# ETAG_v8_u2270b_AOS2017.net
KiCad netlist of a schematic drawn in EAGLE
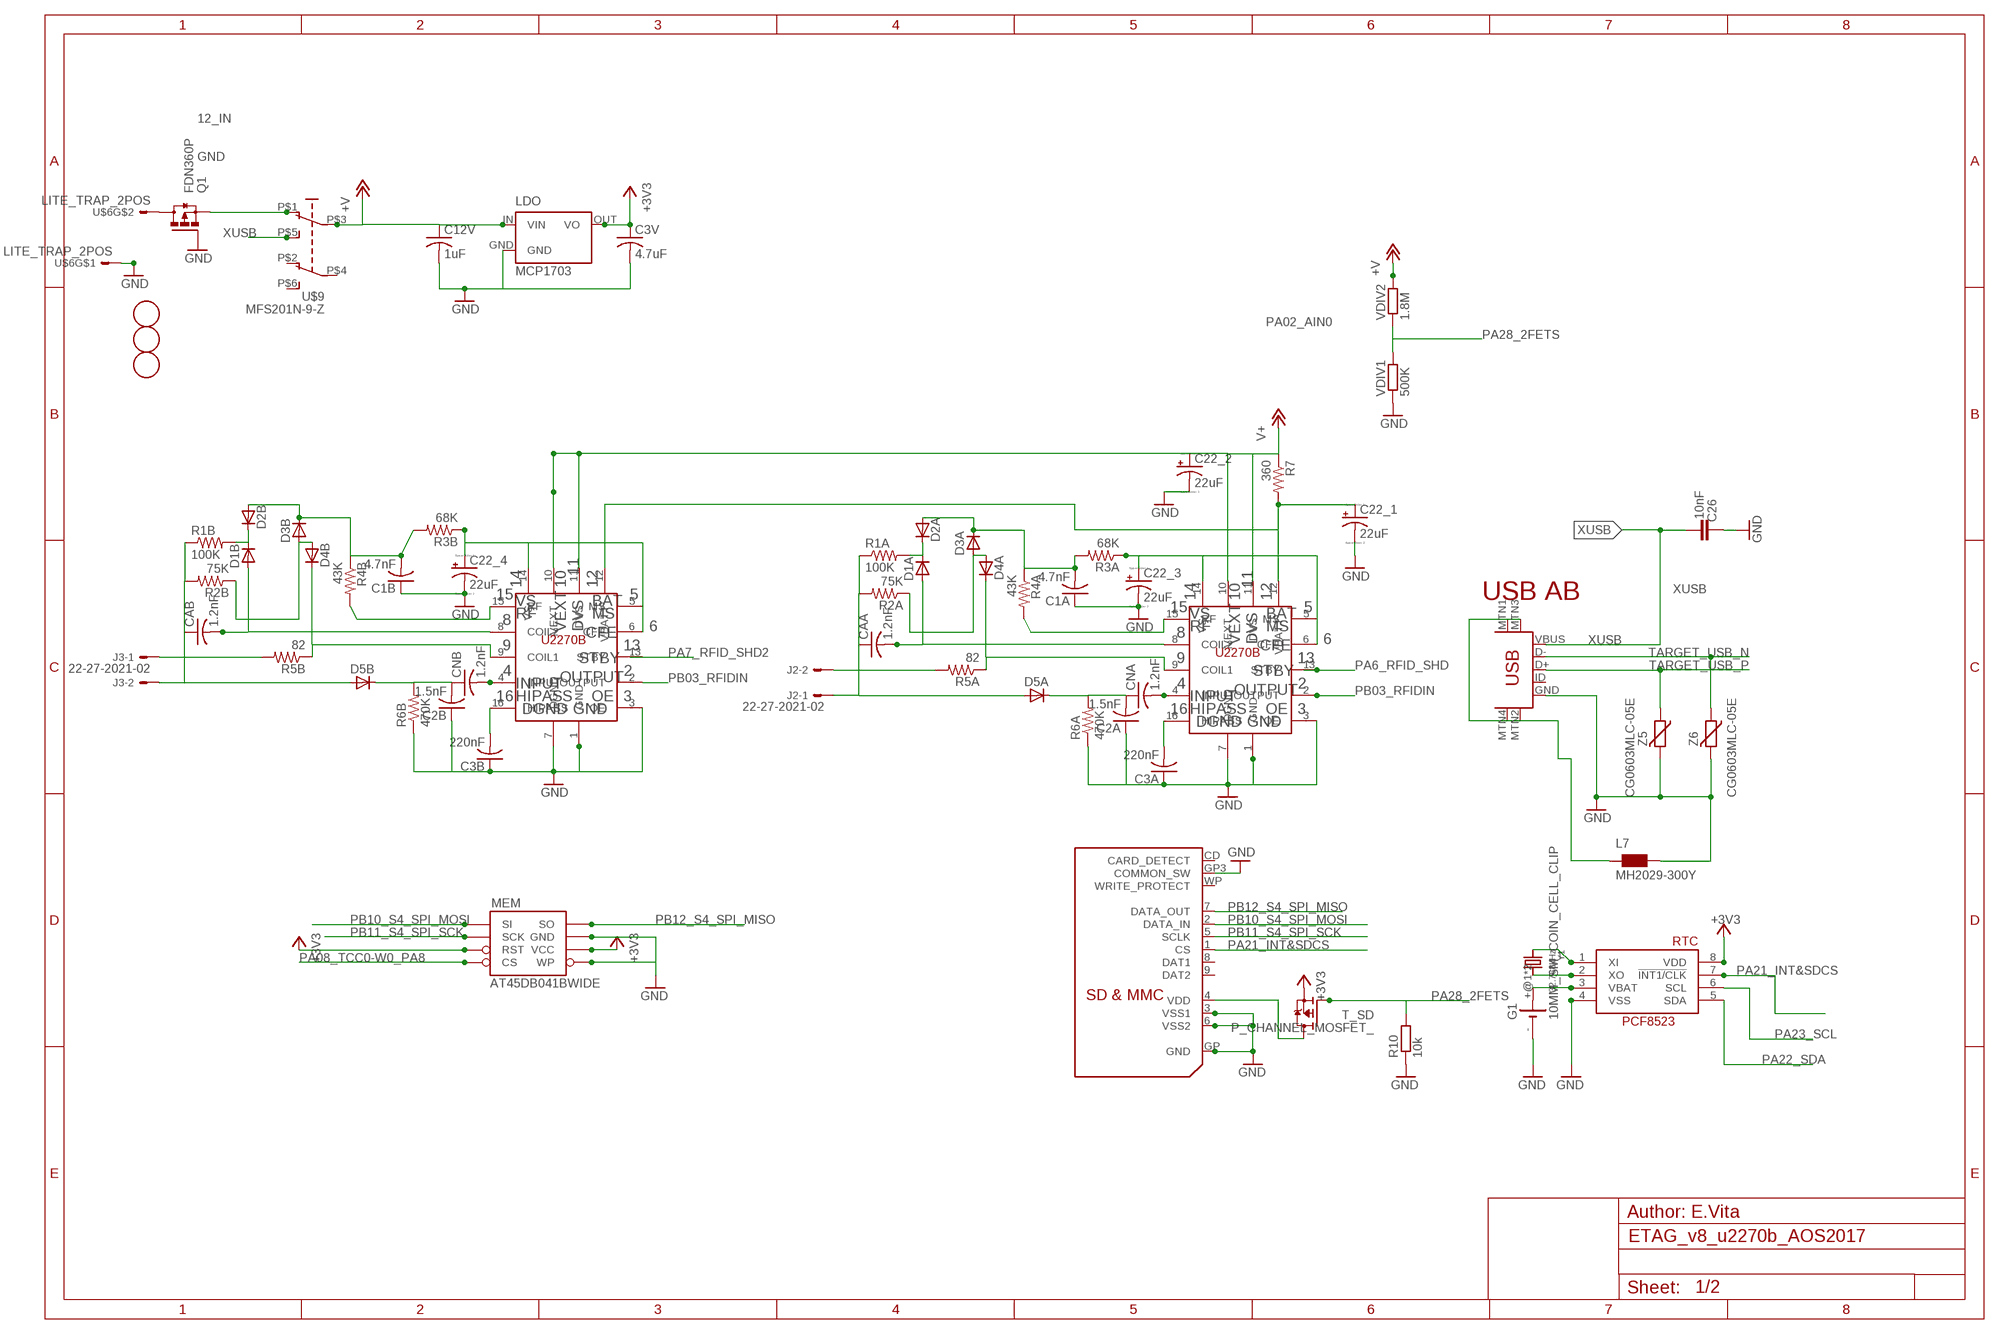
[diagram p0: schematic, sheet 1]
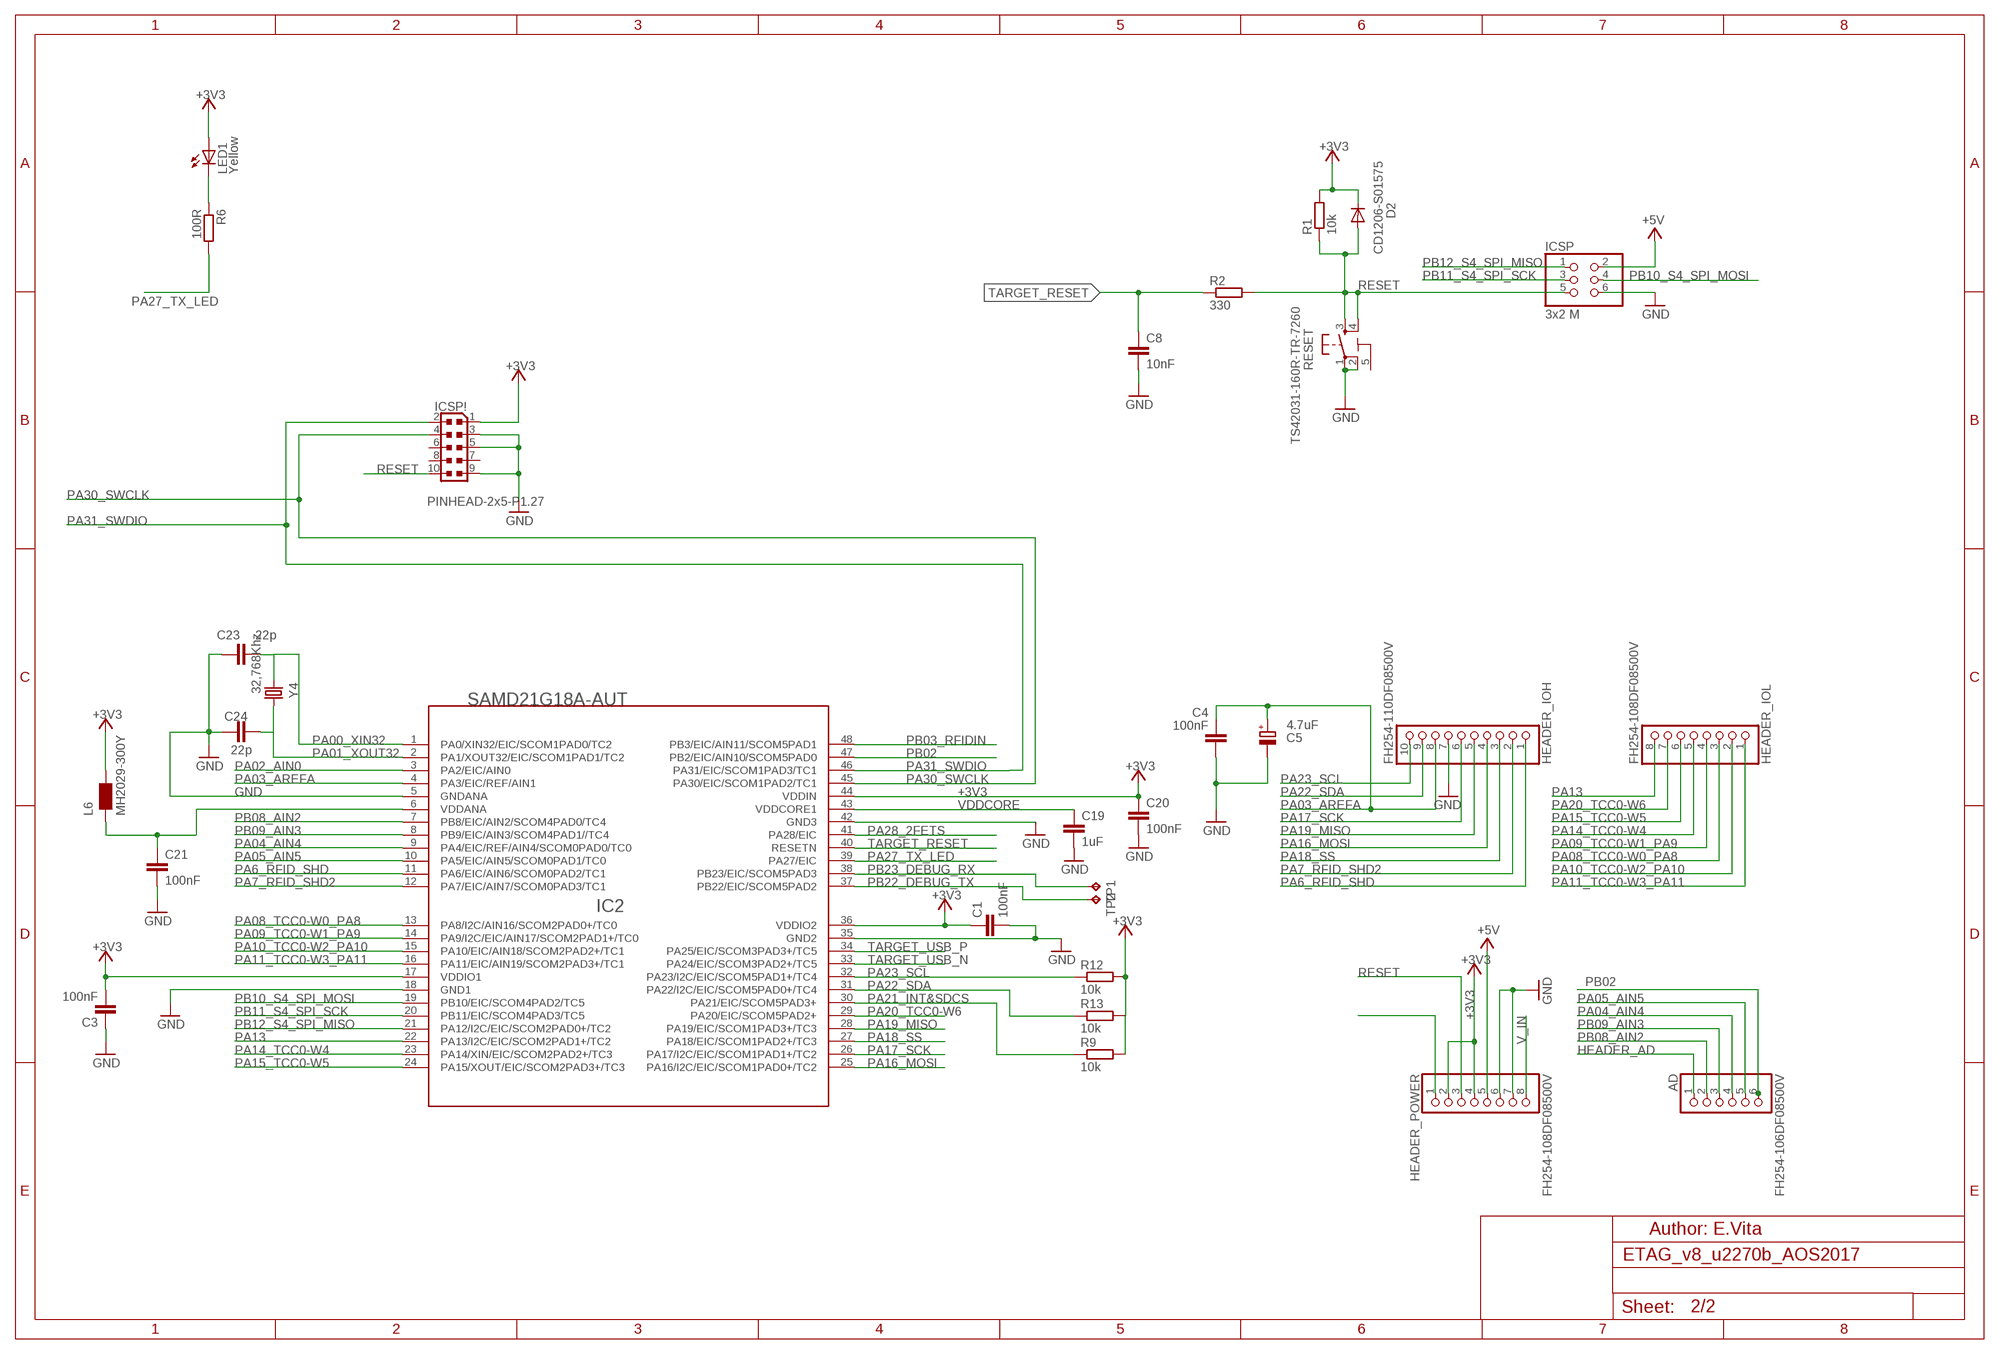
[diagram p1: schematic, sheet 2]

(export (version "E")
  (design (tool "Eeschema 10.0.6"))
  (components
    (comp (ref "AD")
      (value "FH254-106DF08500V")
      (footprint "eagle-import:1X06")
      (fields (field (name "PART_NUMBER") "20TW-535"))
      (libsource (lib "eagle-import") (part "1682_20TW-535_STD"))
    )
    (comp (ref "C1")
      (value "100nF")
      (footprint "eagle-import:C0603-ROUND")
      (fields (field (name "PART_NUMBER") "cl10b104kbnc"))
      (libsource (lib "eagle-import") (part "0015_100NF_0603"))
    )
    (comp (ref "C3")
      (value "100nF")
      (footprint "eagle-import:C0603-ROUND")
      (fields (field (name "PART_NUMBER") "cl10b104kbnc"))
      (libsource (lib "eagle-import") (part "0015_100NF_0603"))
    )
    (comp (ref "C4")
      (value "100nF")
      (footprint "eagle-import:C0603-ROUND")
      (fields (field (name "PART_NUMBER") "cl10b104kbnc"))
      (libsource (lib "eagle-import") (part "0015_100NF_0603"))
    )
    (comp (ref "C5")
      (value "4.7uF")
      (footprint "eagle-import:SMC_A")
      (fields (field (name "PART_NUMBER") "TAJA475M016RNJ"))
      (libsource (lib "eagle-import") (part "0474_TAJA475M016RNJ"))
    )
    (comp (ref "C8")
      (value "10nF")
      (footprint "eagle-import:C0603-ROUND")
      (fields (field (name "PART_NUMBER") "10nF_0603"))
      (libsource (lib "eagle-import") (part "0142_10NF_0603"))
    )
    (comp (ref "C19")
      (value "1uF")
      (footprint "eagle-import:C0603-ROUND")
      (fields (field (name "PART_NUMBER") "1uF_0603/GRM188R61E105KA12D"))
      (libsource (lib "eagle-import") (part "0006_1UF_0603/GRM188R61E105KA12D"))
    )
    (comp (ref "C20")
      (value "100nF")
      (footprint "eagle-import:C0603-ROUND")
      (fields (field (name "PART_NUMBER") "cl10b104kbnc"))
      (libsource (lib "eagle-import") (part "0015_100NF_0603"))
    )
    (comp (ref "C21")
      (value "100nF")
      (footprint "eagle-import:C0603-ROUND")
      (fields (field (name "PART_NUMBER") "cl10b104kbnc"))
      (libsource (lib "eagle-import") (part "0015_100NF_0603"))
    )
    (comp (ref "C23")
      (value "22p")
      (footprint "eagle-import:C0603-ROUND")
      (fields (field (name "PART_NUMBER") "22pF_0603"))
      (libsource (lib "eagle-import") (part "0014_22PF_0603"))
    )
    (comp (ref "C24")
      (value "22p")
      (footprint "eagle-import:C0603-ROUND")
      (fields (field (name "PART_NUMBER") "22pF_0603"))
      (libsource (lib "eagle-import") (part "0014_22PF_0603"))
    )
    (comp (ref "D2")
      (value "CD1206-S01575")
      (footprint "eagle-import:MINIMELF")
      (libsource (lib "eagle-import") (part "0012_CD1206-S01575"))
    )
    (comp (ref "HEADER_IOH")
      (value "FH254-110DF08500V")
      (footprint "eagle-import:1X10")
      (fields (field (name "PART_NUMBER") "20TW-537"))
      (libsource (lib "eagle-import") (part "1684_20TW-537"))
    )
    (comp (ref "HEADER_IOL")
      (value "FH254-108DF08500V")
      (footprint "eagle-import:1X08")
      (fields (field (name "PART_NUMBER") "20TW-536"))
      (libsource (lib "eagle-import") (part "1683_20TW-536"))
    )
    (comp (ref "HEADER_POWER")
      (value "FH254-108DF08500V")
      (footprint "eagle-import:1X08")
      (fields (field (name "PART_NUMBER") "20TW-536"))
      (libsource (lib "eagle-import") (part "1683_20TW-536"))
    )
    (comp (ref "IC2")
      (value "SAMD21G18A-AUT")
      (footprint "eagle-import:TQFP48-7X7")
      (libsource (lib "eagle-import") (part "1792_SAMD21G18A-AUT"))
    )
    (comp (ref "ICSP")
      (value "3x2 M")
      (footprint "eagle-import:2X03")
      (fields (field (name "PART_NUMBER") "PH254-203DF118A00V"))
      (libsource (lib "eagle-import") (part "0114_PH254-203DF118A00V"))
    )
    (comp (ref "ICSP!")
      (value "PINHEAD-2x5-P1.27")
      (footprint "eagle-import:PINHEAD_2X05_127")
      (libsource (lib "eagle-import") (part "0171_PH127-205DF055G00AROUND-PADS"))
    )
    (comp (ref "L6")
      (value "MH2029-300Y")
      (footprint "eagle-import:0805")
      (fields (field (name "PART_NUMBER") "BLM21PG300SN1D_/_MH2029-300Y"))
      (libsource (lib "eagle-import") (part "0001_BLM21PG300SN1D_/_MH2029-300Y"))
    )
    (comp (ref "LED1")
      (value "Yellow")
      (footprint "eagle-import:CHIPLED_0805")
      (fields (field (name "PART_NUMBER") "KPT-2012YC"))
      (libsource (lib "eagle-import") (part "0044_KPT-2012YC"))
    )
    (comp (ref "R1")
      (value "10k")
      (footprint "eagle-import:R0603-ROUND")
      (fields (field (name "PART_NUMBER") "CR0603JW103L"))
      (libsource (lib "eagle-import") (part "0028_CR0603JW103L"))
    )
    (comp (ref "R2")
      (value "330")
      (footprint "eagle-import:R0603-ROUND")
      (fields (field (name "PART_NUMBER") "330R_0603"))
      (libsource (lib "eagle-import") (part "0049_330R_0603"))
    )
    (comp (ref "R6")
      (value "100R")
      (footprint "eagle-import:R0603-ROUND")
      (fields (field (name "PART_NUMBER") "0R_0603"))
      (libsource (lib "eagle-import") (part "0233_0R_0603"))
    )
    (comp (ref "R9")
      (value "10k")
      (footprint "eagle-import:R0603-ROUND")
      (fields (field (name "PART_NUMBER") "CR0603JW103L"))
      (libsource (lib "eagle-import") (part "0028_CR0603JW103L"))
    )
    (comp (ref "R12")
      (value "10k")
      (footprint "eagle-import:R0603-ROUND")
      (fields (field (name "PART_NUMBER") "CR0603JW103L"))
      (libsource (lib "eagle-import") (part "0028_CR0603JW103L"))
    )
    (comp (ref "R13")
      (value "10k")
      (footprint "eagle-import:R0603-ROUND")
      (fields (field (name "PART_NUMBER") "CR0603JW103L"))
      (libsource (lib "eagle-import") (part "0028_CR0603JW103L"))
    )
    (comp (ref "RESET")
      (value "TS42031-160R-TR-7260")
      (footprint "eagle-import:TS42")
      (fields (field (name "PART_NUMBER") "IT-1157AHNP-160G-G_GTR"))
      (libsource (lib "eagle-import") (part "0946_TS42031-160W-TR-7260"))
    )
    (comp (ref "TP1")
      (value "TPTP15R")
      (footprint "eagle-import:TP15R")
      (libsource (lib "eagle-import") (part "TPTP15R"))
    )
    (comp (ref "TP2")
      (value "TPTP15R")
      (footprint "eagle-import:TP15R")
      (libsource (lib "eagle-import") (part "TPTP15R"))
    )
    (comp (ref "Y4")
      (value "32,768Khz")
      (footprint "eagle-import:RESONATOR_EPSON_FC_145")
      (fields (field (name "PART_NUMBER") "ABS07-32.768KHZ-T"))
      (libsource (lib "eagle-import") (part "0213_ABS07-32.768KHZ-T"))
    )
    (comp (ref "C1A")
      (value "4.7nF")
      (footprint "eagle-import:C0603-ROUND")
      (libsource (lib "eagle-import") (part "C-US"))
    )
    (comp (ref "C1B")
      (value "4.7nF")
      (footprint "eagle-import:C0603-ROUND")
      (libsource (lib "eagle-import") (part "C-US"))
    )
    (comp (ref "C2A")
      (value "1.5nF")
      (footprint "eagle-import:C0805")
      (libsource (lib "eagle-import") (part "C-USC0805"))
    )
    (comp (ref "C2B")
      (value "1.5nF")
      (footprint "eagle-import:C0805")
      (libsource (lib "eagle-import") (part "C-USC0805"))
    )
    (comp (ref "C3A")
      (value "220nF")
      (footprint "eagle-import:C0603-ROUND")
      (libsource (lib "eagle-import") (part "C-US"))
    )
    (comp (ref "C3B")
      (value "220nF")
      (footprint "eagle-import:C0603-ROUND")
      (libsource (lib "eagle-import") (part "C-US"))
    )
    (comp (ref "C3V")
      (value "4.7uF")
      (footprint "eagle-import:C0805")
      (libsource (lib "eagle-import") (part "C-USC0805"))
    )
    (comp (ref "C12V")
      (value "1uF")
      (footprint "eagle-import:C0805")
      (libsource (lib "eagle-import") (part "C-USC0805"))
    )
    (comp (ref "C22_1")
      (value "22uF")
      (footprint "eagle-import:153CLV-0505")
      (libsource (lib "eagle-import") (part "CPOL-US153CLV-0505"))
    )
    (comp (ref "C22_2")
      (value "22uF")
      (footprint "eagle-import:153CLV-0505")
      (libsource (lib "eagle-import") (part "CPOL-US153CLV-0505"))
    )
    (comp (ref "C22_3")
      (value "22uF")
      (footprint "eagle-import:153CLV-0505")
      (libsource (lib "eagle-import") (part "CPOL-US153CLV-0505"))
    )
    (comp (ref "C22_4")
      (value "22uF")
      (footprint "eagle-import:153CLV-0505")
      (libsource (lib "eagle-import") (part "CPOL-US153CLV-0505"))
    )
    (comp (ref "C26")
      (value "10nF")
      (footprint "eagle-import:C0603-ROUND")
      (fields (field (name "PART_NUMBER") "10nF_0603"))
      (libsource (lib "eagle-import") (part "0142_10NF_0603"))
    )
    (comp (ref "CAA")
      (value "1.2nF")
      (footprint "eagle-import:C0805")
      (libsource (lib "eagle-import") (part "C-USC0805"))
    )
    (comp (ref "CAB")
      (value "1.2nF")
      (footprint "eagle-import:C0805")
      (libsource (lib "eagle-import") (part "C-USC0805"))
    )
    (comp (ref "CNA")
      (value "1.2nF")
      (footprint "eagle-import:C0805")
      (libsource (lib "eagle-import") (part "C-USC0805"))
    )
    (comp (ref "CNB")
      (value "1.2nF")
      (footprint "eagle-import:C0805")
      (libsource (lib "eagle-import") (part "C-USC0805"))
    )
    (comp (ref "D1A")
      (value "D-GLASS_MELF")
      (footprint "eagle-import:SOT-23_2PAD")
      (libsource (lib "eagle-import") (part "D-GLASS_MELF"))
    )
    (comp (ref "D1B")
      (value "D-GLASS_MELF")
      (footprint "eagle-import:SOT-23_2PAD")
      (libsource (lib "eagle-import") (part "D-GLASS_MELF"))
    )
    (comp (ref "D2A")
      (value "D-GLASS_MELF")
      (footprint "eagle-import:SOT-23_2PAD")
      (libsource (lib "eagle-import") (part "D-GLASS_MELF"))
    )
    (comp (ref "D2B")
      (value "D-GLASS_MELF")
      (footprint "eagle-import:SOT-23_2PAD")
      (libsource (lib "eagle-import") (part "D-GLASS_MELF"))
    )
    (comp (ref "D3A")
      (value "D-GLASS_MELF")
      (footprint "eagle-import:SOT-23_2PAD")
      (libsource (lib "eagle-import") (part "D-GLASS_MELF"))
    )
    (comp (ref "D3B")
      (value "D-GLASS_MELF")
      (footprint "eagle-import:SOT-23_2PAD")
      (libsource (lib "eagle-import") (part "D-GLASS_MELF"))
    )
    (comp (ref "D4A")
      (value "D-GLASS_MELF")
      (footprint "eagle-import:SOT-23_2PAD")
      (libsource (lib "eagle-import") (part "D-GLASS_MELF"))
    )
    (comp (ref "D4B")
      (value "D-GLASS_MELF")
      (footprint "eagle-import:SOT-23_2PAD")
      (libsource (lib "eagle-import") (part "D-GLASS_MELF"))
    )
    (comp (ref "D5A")
      (value "D-GLASS_MELF")
      (footprint "eagle-import:SOT-23_2PAD")
      (libsource (lib "eagle-import") (part "D-GLASS_MELF"))
    )
    (comp (ref "D5B")
      (value "D-GLASS_MELF")
      (footprint "eagle-import:SOT-23_2PAD")
      (libsource (lib "eagle-import") (part "D-GLASS_MELF"))
    )
    (comp (ref "FD1")
      (value "FIDUCIALMOUNT")
      (footprint "eagle-import:FIDUCIA-MOUNT")
      (libsource (lib "eagle-import") (part "FIDUCIALMOUNT"))
    )
    (comp (ref "FD2")
      (value "FIDUCIALMOUNT")
      (footprint "eagle-import:FIDUCIA-MOUNT")
      (libsource (lib "eagle-import") (part "FIDUCIALMOUNT"))
    )
    (comp (ref "FD3")
      (value "FIDUCIALMOUNT")
      (footprint "eagle-import:FIDUCIA-MOUNT")
      (libsource (lib "eagle-import") (part "FIDUCIALMOUNT"))
    )
    (comp (ref "G1")
      (value "10MM_SM_COIN_CELL_CLIP")
      (footprint "eagle-import:10MM_SM_COIN_CELL_CLIP")
      (libsource (lib "eagle-import") (part "10MM_SM_COIN_CELL_CLIP"))
    )
    (comp (ref "J2")
      (value "22-27-2021-02")
      (footprint "eagle-import:6410-02")
      (libsource (lib "eagle-import") (part "22-?-0227-2021"))
    )
    (comp (ref "J3")
      (value "22-27-2021-02")
      (footprint "eagle-import:6410-02")
      (libsource (lib "eagle-import") (part "22-?-0227-2021"))
    )
    (comp (ref "L7")
      (value "MH2029-300Y")
      (footprint "eagle-import:0805")
      (fields (field (name "PART_NUMBER") "BLM21PG300SN1D_/_MH2029-300Y"))
      (libsource (lib "eagle-import") (part "0001_BLM21PG300SN1D_/_MH2029-300Y"))
    )
    (comp (ref "LDO")
      (value "MCP1703")
      (footprint "eagle-import:SOT89")
      (libsource (lib "eagle-import") (part "MCP1703"))
    )
    (comp (ref "MEM")
      (value "AT45DB041BWIDE")
      (footprint "eagle-import:SO08WIDE")
      (libsource (lib "eagle-import") (part "AT45DB041BWIDE"))
    )
    (comp (ref "Q1")
      (value "FDN360P")
      (footprint "eagle-import:SUPER-SOT3")
      (libsource (lib "eagle-import") (part "FDN360P"))
    )
    (comp (ref "R1A")
      (value "100K")
      (footprint "eagle-import:C0603-ROUND")
      (libsource (lib "eagle-import") (part "R-US_ROUND"))
    )
    (comp (ref "R1B")
      (value "100K")
      (footprint "eagle-import:C0603-ROUND")
      (libsource (lib "eagle-import") (part "R-US_ROUND"))
    )
    (comp (ref "R2A")
      (value "75K")
      (footprint "eagle-import:C0603-ROUND")
      (libsource (lib "eagle-import") (part "R-US_ROUND"))
    )
    (comp (ref "R2B")
      (value "75K")
      (footprint "eagle-import:C0603-ROUND")
      (libsource (lib "eagle-import") (part "R-US_ROUND"))
    )
    (comp (ref "R3A")
      (value "68K")
      (footprint "eagle-import:C0603-ROUND")
      (libsource (lib "eagle-import") (part "R-US_ROUND"))
    )
    (comp (ref "R3B")
      (value "68K")
      (footprint "eagle-import:C0603-ROUND")
      (libsource (lib "eagle-import") (part "R-US_ROUND"))
    )
    (comp (ref "R4A")
      (value "43K")
      (footprint "eagle-import:C0603-ROUND")
      (libsource (lib "eagle-import") (part "R-US_ROUND"))
    )
    (comp (ref "R4B")
      (value "43K")
      (footprint "eagle-import:C0603-ROUND")
      (libsource (lib "eagle-import") (part "R-US_ROUND"))
    )
    (comp (ref "R5A")
      (value "82")
      (footprint "eagle-import:C0603-ROUND")
      (libsource (lib "eagle-import") (part "R-US_ROUND"))
    )
    (comp (ref "R5B")
      (value "82")
      (footprint "eagle-import:C0603-ROUND")
      (libsource (lib "eagle-import") (part "R-US_ROUND"))
    )
    (comp (ref "R6A")
      (value "470K")
      (footprint "eagle-import:C0603-ROUND")
      (libsource (lib "eagle-import") (part "R-US_ROUND"))
    )
    (comp (ref "R6B")
      (value "470K")
      (footprint "eagle-import:C0603-ROUND")
      (libsource (lib "eagle-import") (part "R-US_ROUND"))
    )
    (comp (ref "R7")
      (value "360")
      (footprint "eagle-import:C0603-ROUND")
      (libsource (lib "eagle-import") (part "R-US_ROUND"))
    )
    (comp (ref "R10")
      (value "10k")
      (footprint "eagle-import:R0603-ROUND")
      (fields (field (name "PART_NUMBER") "CR0603JW103L"))
      (libsource (lib "eagle-import") (part "0028_CR0603JW103L"))
    )
    (comp (ref "RF_A")
      (value "U2270B")
      (footprint "eagle-import:SO16")
      (libsource (lib "eagle-import") (part "U2270B"))
    )
    (comp (ref "RF_B")
      (value "U2270B")
      (footprint "eagle-import:SO16")
      (libsource (lib "eagle-import") (part "U2270B"))
    )
    (comp (ref "RTC")
      (value "RTC_PCF8523T")
      (footprint "eagle-import:SOIC8_150MIL")
      (libsource (lib "eagle-import") (part "RTC_PCF8523T"))
    )
    (comp (ref "T_SD")
      (value "P_CHANNEL_MOSFET_")
      (footprint "eagle-import:SOT23")
      (libsource (lib "eagle-import") (part "P_CHANNEL_MOSFET_"))
    )
    (comp (ref "U$4")
      (value "SDMMC06132")
      (footprint "eagle-import:06132")
      (libsource (lib "eagle-import") (part "SDMMC06132"))
    )
    (comp (ref "U$6")
      (value "LITE_TRAP_2POS")
      (footprint "eagle-import:LITE_TRAP_MINI")
      (libsource (lib "eagle-import") (part "LITE_TRAP_2POS"))
    )
    (comp (ref "U$9")
      (value "MFS201N-9-Z")
      (footprint "eagle-import:MFS201N-9-Z")
      (libsource (lib "eagle-import") (part "MFS201N-9-Z"))
    )
    (comp (ref "USB")
      (value "USB-MINIB-5PIN")
      (footprint "eagle-import:USB-MINIB")
      (libsource (lib "eagle-import") (part "USB-MINIB-5PIN"))
    )
    (comp (ref "VDIV1")
      (value "500K")
      (footprint "eagle-import:R0603-ROUND")
      (libsource (lib "eagle-import") (part "2339_"))
    )
    (comp (ref "VDIV2")
      (value "1.8M")
      (footprint "eagle-import:R0603-ROUND")
      (fields (field (name "PART_NUMBER") "CR0603FW104L"))
      (libsource (lib "eagle-import") (part "2022_CR0603FW104L"))
    )
    (comp (ref "Y1")
      (value "32.768kHz")
      (footprint "eagle-import:CRYSTAL_8X3.8")
      (libsource (lib "eagle-import") (part "CRYSTAL8.0X3.8"))
    )
    (comp (ref "Z5")
      (value "CG0603MLC-05E")
      (footprint "eagle-import:CT_CN0603")
      (fields (field (name "PART_NUMBER") "BRNCG0603MLC-05E"))
      (libsource (lib "eagle-import") (part "0010_BRNCG0603MLC-05E"))
    )
    (comp (ref "Z6")
      (value "CG0603MLC-05E")
      (footprint "eagle-import:CT_CN0603")
      (fields (field (name "PART_NUMBER") "BRNCG0603MLC-05E"))
      (libsource (lib "eagle-import") (part "0010_BRNCG0603MLC-05E"))
    )
  )
  (nets
    (net (code "1") (name "+3V3") (class "Default")
      (node (ref "C1") (pin "1") (pinfunction "1_1") (pintype "passive"))
      (node (ref "C20") (pin "1") (pinfunction "1_1") (pintype "passive"))
      (node (ref "C3") (pin "2") (pinfunction "2_2") (pintype "passive"))
      (node (ref "C3V") (pin "1") (pinfunction "1_1") (pintype "passive"))
      (node (ref "D2") (pin "C") (pinfunction "C_C") (pintype "passive"))
      (node (ref "HEADER_POWER") (pin "2") (pinfunction "2_2") (pintype "passive"))
      (node (ref "HEADER_POWER") (pin "4") (pinfunction "4_4") (pintype "passive"))
      (node (ref "IC2") (pin "17") (pinfunction "VDDIO1_17") (pintype "power_in"))
      (node (ref "IC2") (pin "36") (pinfunction "VDDIO2_36") (pintype "power_in"))
      (node (ref "IC2") (pin "44") (pinfunction "VDDIN_44") (pintype "power_in"))
      (node (ref "ICSP!") (pin "1") (pinfunction "1_1") (pintype "passive"))
      (node (ref "L6") (pin "2") (pinfunction "2_2") (pintype "passive"))
      (node (ref "LDO") (pin "OUT") (pinfunction "VO_OUT") (pintype "output"))
      (node (ref "LED1") (pin "A") (pinfunction "A_A") (pintype "passive"))
      (node (ref "MEM") (pin "3") (pinfunction "RST_3") (pintype "bidirectional"))
      (node (ref "MEM") (pin "6") (pinfunction "VCC_6") (pintype "bidirectional"))
      (node (ref "R1") (pin "2") (pinfunction "2_2") (pintype "passive"))
      (node (ref "R12") (pin "2") (pinfunction "2_2") (pintype "passive"))
      (node (ref "R13") (pin "2") (pinfunction "2_2") (pintype "passive"))
      (node (ref "R9") (pin "2") (pinfunction "2_2") (pintype "passive"))
      (node (ref "RTC") (pin "8") (pinfunction "VDD_8") (pintype "power_in"))
      (node (ref "T_SD") (pin "2") (pinfunction "S_2") (pintype "passive"))
    )
    (net (code "2") (name "+5V") (class "Default")
      (node (ref "HEADER_POWER") (pin "5") (pinfunction "5_5") (pintype "passive"))
      (node (ref "ICSP") (pin "2") (pinfunction "2_2") (pintype "passive"))
    )
    (net (code "3") (name "5-GND") (class "Default")
      (node (ref "RESET") (pin "5") (pinfunction "5-GND_5") (pintype "power_in"))
    )
    (net (code "5") (name "12_IN") (class "Default")
      (node (ref "Q1") (pin "3") (pinfunction "D_3") (pintype "passive"))
      (node (ref "U$6") (pin "P$3") (pinfunction "S_P$3") (pintype "passive"))
      (node (ref "U$6") (pin "P$4") (pinfunction "S_P$4") (pintype "passive"))
    )
    (net (code "6") (name "GND") (class "Default")
      (node (ref "C1") (pin "2") (pinfunction "2_2") (pintype "passive"))
      (node (ref "C12V") (pin "2") (pinfunction "2_2") (pintype "passive"))
      (node (ref "C19") (pin "2") (pinfunction "2_2") (pintype "passive"))
      (node (ref "C1A") (pin "1") (pinfunction "1_1") (pintype "passive"))
      (node (ref "C1B") (pin "1") (pinfunction "1_1") (pintype "passive"))
      (node (ref "C20") (pin "2") (pinfunction "2_2") (pintype "passive"))
      (node (ref "C21") (pin "2") (pinfunction "2_2") (pintype "passive"))
      (node (ref "C22_1") (pin "-") (pinfunction "-_-") (pintype "passive"))
      (node (ref "C22_2") (pin "-") (pinfunction "-_-") (pintype "passive"))
      (node (ref "C22_3") (pin "-") (pinfunction "-_-") (pintype "passive"))
      (node (ref "C22_4") (pin "-") (pinfunction "-_-") (pintype "passive"))
      (node (ref "C23") (pin "1") (pinfunction "1_1") (pintype "passive"))
      (node (ref "C24") (pin "1") (pinfunction "1_1") (pintype "passive"))
      (node (ref "C26") (pin "2") (pinfunction "2_2") (pintype "passive"))
      (node (ref "C2A") (pin "1") (pinfunction "1_1") (pintype "passive"))
      (node (ref "C2B") (pin "1") (pinfunction "1_1") (pintype "passive"))
      (node (ref "C3") (pin "1") (pinfunction "1_1") (pintype "passive"))
      (node (ref "C3A") (pin "1") (pinfunction "1_1") (pintype "passive"))
      (node (ref "C3B") (pin "1") (pinfunction "1_1") (pintype "passive"))
      (node (ref "C3V") (pin "2") (pinfunction "2_2") (pintype "passive"))
      (node (ref "C4") (pin "2") (pinfunction "2_2") (pintype "passive"))
      (node (ref "C5") (pin "-") (pinfunction "-_-") (pintype "passive"))
      (node (ref "C8") (pin "2") (pinfunction "2_2") (pintype "passive"))
      (node (ref "G1") (pin "-") (pinfunction "-_-") (pintype "passive"))
      (node (ref "HEADER_IOH") (pin "7") (pinfunction "7_7") (pintype "passive"))
      (node (ref "HEADER_POWER") (pin "6") (pinfunction "6_6") (pintype "passive"))
      (node (ref "HEADER_POWER") (pin "7") (pinfunction "7_7") (pintype "passive"))
      (node (ref "IC2") (pin "18") (pinfunction "GND1_18") (pintype "power_in"))
      (node (ref "IC2") (pin "35") (pinfunction "GND2_35") (pintype "power_in"))
      (node (ref "IC2") (pin "42") (pinfunction "GND3_42") (pintype "power_in"))
      (node (ref "IC2") (pin "5") (pinfunction "GNDANA_5") (pintype "power_in"))
      (node (ref "ICSP") (pin "6") (pinfunction "6_6") (pintype "passive"))
      (node (ref "ICSP!") (pin "3") (pinfunction "3_3") (pintype "passive"))
      (node (ref "ICSP!") (pin "5") (pinfunction "5_5") (pintype "passive"))
      (node (ref "ICSP!") (pin "9") (pinfunction "9_9") (pintype "passive"))
      (node (ref "L7") (pin "2") (pinfunction "2_2") (pintype "passive"))
      (node (ref "LDO") (pin "GND") (pinfunction "GND_GND") (pintype "passive"))
      (node (ref "MEM") (pin "5") (pinfunction "WP_5") (pintype "bidirectional"))
      (node (ref "MEM") (pin "7") (pinfunction "GND_7") (pintype "bidirectional"))
      (node (ref "Q1") (pin "1") (pinfunction "G_1") (pintype "passive"))
      (node (ref "R10") (pin "1") (pinfunction "1_1") (pintype "passive"))
      (node (ref "R6A") (pin "1") (pinfunction "1_1") (pintype "passive"))
      (node (ref "R6B") (pin "1") (pinfunction "1_1") (pintype "passive"))
      (node (ref "RESET") (pin "1") (pinfunction "1_1") (pintype "passive"))
      (node (ref "RESET") (pin "2") (pinfunction "2_2") (pintype "passive"))
      (node (ref "RF_A") (pin "1") (pinfunction "GND_1") (pintype "bidirectional"))
      (node (ref "RF_A") (pin "3") (pinfunction "OE_3") (pintype "bidirectional"))
      (node (ref "RF_A") (pin "7") (pinfunction "DGND_7") (pintype "bidirectional"))
      (node (ref "RF_B") (pin "1") (pinfunction "GND_1") (pintype "bidirectional"))
      (node (ref "RF_B") (pin "3") (pinfunction "OE_3") (pintype "bidirectional"))
      (node (ref "RF_B") (pin "7") (pinfunction "DGND_7") (pintype "bidirectional"))
      (node (ref "RTC") (pin "4") (pinfunction "VSS_4") (pintype "power_in"))
      (node (ref "U$4") (pin "3") (pinfunction "VSS1_3") (pintype "power_in"))
      (node (ref "U$4") (pin "6") (pinfunction "VSS2_6") (pintype "power_in"))
      (node (ref "U$4") (pin "GP") (pinfunction "GND_GP") (pintype "power_in"))
      (node (ref "U$4") (pin "GP3") (pinfunction "COMMON_SW_GP3") (pintype "passive"))
      (node (ref "U$6") (pin "P$1") (pinfunction "S_P$1") (pintype "passive"))
      (node (ref "U$6") (pin "P$2") (pinfunction "S_P$2") (pintype "passive"))
      (node (ref "USB") (pin "GND") (pinfunction "GND_GND") (pintype "bidirectional"))
      (node (ref "VDIV1") (pin "1") (pinfunction "1_1") (pintype "passive"))
      (node (ref "Z5") (pin "2") (pinfunction "2_2") (pintype "passive"))
      (node (ref "Z6") (pin "2") (pinfunction "2_2") (pintype "passive"))
    )
    (net (code "7") (name "HEADER_AD") (class "Default")
      (node (ref "AD") (pin "1") (pinfunction "1_1") (pintype "passive"))
    )
    (net (code "8") (name "Net-(D1A-A)") (class "Default")
      (node (ref "CAA") (pin "2") (pinfunction "2_2") (pintype "passive"))
      (node (ref "D1A") (pin "P$2") (pinfunction "A_P$2") (pintype "passive"))
      (node (ref "RF_A") (pin "8") (pinfunction "COIL2_8") (pintype "bidirectional"))
    )
    (net (code "9") (name "Net-(D1A-C)") (class "Default")
      (node (ref "D1A") (pin "P$1") (pinfunction "C_P$1") (pintype "passive"))
      (node (ref "D2A") (pin "P$1") (pinfunction "C_P$1") (pintype "passive"))
      (node (ref "R1A") (pin "2") (pinfunction "2_2") (pintype "passive"))
    )
    (net (code "10") (name "Net-(D1B-A)") (class "Default")
      (node (ref "CAB") (pin "2") (pinfunction "2_2") (pintype "passive"))
      (node (ref "D1B") (pin "P$2") (pinfunction "A_P$2") (pintype "passive"))
      (node (ref "RF_B") (pin "8") (pinfunction "COIL2_8") (pintype "bidirectional"))
    )
    (net (code "11") (name "Net-(D1B-C)") (class "Default")
      (node (ref "D1B") (pin "P$1") (pinfunction "C_P$1") (pintype "passive"))
      (node (ref "D2B") (pin "P$1") (pinfunction "C_P$1") (pintype "passive"))
      (node (ref "R1B") (pin "2") (pinfunction "2_2") (pintype "passive"))
    )
    (net (code "12") (name "Net-(D2A-A)") (class "Default")
      (node (ref "C1A") (pin "2") (pinfunction "2_2") (pintype "passive"))
      (node (ref "D2A") (pin "P$2") (pinfunction "A_P$2") (pintype "passive"))
      (node (ref "D3A") (pin "P$1") (pinfunction "C_P$1") (pintype "passive"))
      (node (ref "R3A") (pin "2") (pinfunction "2_2") (pintype "passive"))
      (node (ref "R4A") (pin "1") (pinfunction "1_1") (pintype "passive"))
    )
    (net (code "13") (name "Net-(D2B-A)") (class "Default")
      (node (ref "C1B") (pin "2") (pinfunction "2_2") (pintype "passive"))
      (node (ref "D2B") (pin "P$2") (pinfunction "A_P$2") (pintype "passive"))
      (node (ref "D3B") (pin "P$1") (pinfunction "C_P$1") (pintype "passive"))
      (node (ref "R3B") (pin "2") (pinfunction "2_2") (pintype "passive"))
      (node (ref "R4B") (pin "1") (pinfunction "1_1") (pintype "passive"))
    )
    (net (code "14") (name "Net-(D3A-A)") (class "Default")
      (node (ref "D3A") (pin "P$2") (pinfunction "A_P$2") (pintype "passive"))
      (node (ref "D4A") (pin "P$2") (pinfunction "A_P$2") (pintype "passive"))
      (node (ref "R2A") (pin "1") (pinfunction "1_1") (pintype "passive"))
    )
    (net (code "15") (name "Net-(D3B-A)") (class "Default")
      (node (ref "D3B") (pin "P$2") (pinfunction "A_P$2") (pintype "passive"))
      (node (ref "D4B") (pin "P$2") (pinfunction "A_P$2") (pintype "passive"))
      (node (ref "R2B") (pin "1") (pinfunction "1_1") (pintype "passive"))
    )
    (net (code "16") (name "Net-(D4A-C)") (class "Default")
      (node (ref "D4A") (pin "P$1") (pinfunction "C_P$1") (pintype "passive"))
      (node (ref "R5A") (pin "1") (pinfunction "1_1") (pintype "passive"))
      (node (ref "RF_A") (pin "9") (pinfunction "COIL1_9") (pintype "bidirectional"))
    )
    (net (code "17") (name "Net-(D4B-C)") (class "Default")
      (node (ref "D4B") (pin "P$1") (pinfunction "C_P$1") (pintype "passive"))
      (node (ref "R5B") (pin "1") (pinfunction "1_1") (pintype "passive"))
      (node (ref "RF_B") (pin "9") (pinfunction "COIL1_9") (pintype "bidirectional"))
    )
    (net (code "18") (name "Net-(D5A-A)") (class "Default")
      (node (ref "CAA") (pin "1") (pinfunction "1_1") (pintype "passive"))
      (node (ref "D5A") (pin "P$2") (pinfunction "A_P$2") (pintype "passive"))
      (node (ref "J2") (pin "1") (pinfunction "S_1") (pintype "passive"))
      (node (ref "R1A") (pin "1") (pinfunction "1_1") (pintype "passive"))
      (node (ref "R2A") (pin "2") (pinfunction "2_2") (pintype "passive"))
    )
    (net (code "19") (name "Net-(D5A-C)") (class "Default")
      (node (ref "C2A") (pin "2") (pinfunction "2_2") (pintype "passive"))
      (node (ref "CNA") (pin "1") (pinfunction "1_1") (pintype "passive"))
      (node (ref "D5A") (pin "P$1") (pinfunction "C_P$1") (pintype "passive"))
      (node (ref "R6A") (pin "2") (pinfunction "2_2") (pintype "passive"))
    )
    (net (code "20") (name "Net-(D5B-A)") (class "Default")
      (node (ref "CAB") (pin "1") (pinfunction "1_1") (pintype "passive"))
      (node (ref "D5B") (pin "P$2") (pinfunction "A_P$2") (pintype "passive"))
      (node (ref "J3") (pin "2") (pinfunction "S_2") (pintype "passive"))
      (node (ref "R1B") (pin "1") (pinfunction "1_1") (pintype "passive"))
      (node (ref "R2B") (pin "2") (pinfunction "2_2") (pintype "passive"))
    )
    (net (code "21") (name "Net-(D5B-C)") (class "Default")
      (node (ref "C2B") (pin "2") (pinfunction "2_2") (pintype "passive"))
      (node (ref "CNB") (pin "1") (pinfunction "1_1") (pintype "passive"))
      (node (ref "D5B") (pin "P$1") (pinfunction "C_P$1") (pintype "passive"))
      (node (ref "R6B") (pin "2") (pinfunction "2_2") (pintype "passive"))
    )
    (net (code "22") (name "Net-(IC2-VDDANA)") (class "Default")
      (node (ref "C21") (pin "1") (pinfunction "1_1") (pintype "passive"))
      (node (ref "IC2") (pin "6") (pinfunction "VDDANA_6") (pintype "power_in"))
      (node (ref "L6") (pin "1") (pinfunction "1_1") (pintype "passive"))
    )
    (net (code "23") (name "Net-(J2B-S)") (class "Default")
      (node (ref "J2") (pin "2") (pinfunction "S_2") (pintype "passive"))
      (node (ref "R5A") (pin "2") (pinfunction "2_2") (pintype "passive"))
    )
    (net (code "24") (name "Net-(J3A-S)") (class "Default")
      (node (ref "J3") (pin "1") (pinfunction "S_1") (pintype "passive"))
      (node (ref "R5B") (pin "2") (pinfunction "2_2") (pintype "passive"))
    )
    (net (code "25") (name "Net-(LED1-PadC)") (class "Default")
      (node (ref "LED1") (pin "C") (pinfunction "C_C") (pintype "passive"))
      (node (ref "R6") (pin "1") (pinfunction "1_1") (pintype "passive"))
    )
    (net (code "26") (name "Net-(Q1-S)") (class "Default")
      (node (ref "Q1") (pin "2") (pinfunction "S_2") (pintype "passive"))
      (node (ref "U$9") (pin "P$1") (pinfunction "O_P$1") (pintype "passive"))
    )
    (net (code "27") (name "Net-(RF_A-CFE)") (class "Default")
      (node (ref "C22_3") (pin "+") (pinfunction "+_+") (pintype "passive"))
      (node (ref "R3A") (pin "1") (pinfunction "1_1") (pintype "passive"))
      (node (ref "RF_A") (pin "14") (pinfunction "VS_14") (pintype "bidirectional"))
      (node (ref "RF_A") (pin "5") (pinfunction "MS_5") (pintype "bidirectional"))
      (node (ref "RF_A") (pin "6") (pinfunction "CFE_6") (pintype "bidirectional"))
    )
    (net (code "28") (name "Net-(RF_A-HIPASS)") (class "Default")
      (node (ref "C3A") (pin "2") (pinfunction "2_2") (pintype "passive"))
      (node (ref "RF_A") (pin "16") (pinfunction "HIPASS_16") (pintype "bidirectional"))
    )
    (net (code "29") (name "Net-(RF_A-INPUT)") (class "Default")
      (node (ref "CNA") (pin "2") (pinfunction "2_2") (pintype "passive"))
      (node (ref "RF_A") (pin "4") (pinfunction "INPUT_4") (pintype "bidirectional"))
    )
    (net (code "30") (name "Net-(RF_A-RF)") (class "Default")
      (node (ref "R4A") (pin "2") (pinfunction "2_2") (pintype "passive"))
      (node (ref "RF_A") (pin "15") (pinfunction "RF_15") (pintype "bidirectional"))
    )
    (net (code "31") (name "Net-(RF_A-VBATT)") (class "Default")
      (node (ref "C22_1") (pin "+") (pinfunction "+_+") (pintype "passive"))
      (node (ref "R7") (pin "2") (pinfunction "2_2") (pintype "passive"))
      (node (ref "RF_A") (pin "12") (pinfunction "VBATT_12") (pintype "bidirectional"))
      (node (ref "RF_B") (pin "12") (pinfunction "VBATT_12") (pintype "bidirectional"))
    )
    (net (code "32") (name "Net-(RF_B-CFE)") (class "Default")
      (node (ref "C22_4") (pin "+") (pinfunction "+_+") (pintype "passive"))
      (node (ref "R3B") (pin "1") (pinfunction "1_1") (pintype "passive"))
      (node (ref "RF_B") (pin "14") (pinfunction "VS_14") (pintype "bidirectional"))
      (node (ref "RF_B") (pin "5") (pinfunction "MS_5") (pintype "bidirectional"))
      (node (ref "RF_B") (pin "6") (pinfunction "CFE_6") (pintype "bidirectional"))
    )
    (net (code "33") (name "Net-(RF_B-HIPASS)") (class "Default")
      (node (ref "C3B") (pin "2") (pinfunction "2_2") (pintype "passive"))
      (node (ref "RF_B") (pin "16") (pinfunction "HIPASS_16") (pintype "bidirectional"))
    )
    (net (code "34") (name "Net-(RF_B-INPUT)") (class "Default")
      (node (ref "CNB") (pin "2") (pinfunction "2_2") (pintype "passive"))
      (node (ref "RF_B") (pin "4") (pinfunction "INPUT_4") (pintype "bidirectional"))
    )
    (net (code "35") (name "Net-(RF_B-RF)") (class "Default")
      (node (ref "R4B") (pin "2") (pinfunction "2_2") (pintype "passive"))
      (node (ref "RF_B") (pin "15") (pinfunction "RF_15") (pintype "bidirectional"))
    )
    (net (code "36") (name "Net-(RTC-VBAT)") (class "Default")
      (node (ref "G1") (pin "+@1") (pinfunction "+_+@1") (pintype "passive"))
      (node (ref "G1") (pin "+@2") (pinfunction "+_+@2") (pintype "passive"))
      (node (ref "RTC") (pin "3") (pinfunction "VBAT_3") (pintype "power_in"))
    )
    (net (code "37") (name "Net-(RTC-XI)") (class "Default")
      (node (ref "RTC") (pin "1") (pinfunction "XI_1") (pintype "input"))
      (node (ref "Y1") (pin "P$1") (pinfunction "1_P$1") (pintype "passive"))
    )
    (net (code "38") (name "Net-(RTC-XO)") (class "Default")
      (node (ref "RTC") (pin "2") (pinfunction "XO_2") (pintype "output"))
      (node (ref "Y1") (pin "P$4") (pinfunction "2_P$4") (pintype "passive"))
    )
    (net (code "39") (name "Net-(T_SD-D)") (class "Default")
      (node (ref "T_SD") (pin "3") (pinfunction "D_3") (pintype "passive"))
      (node (ref "U$4") (pin "4") (pinfunction "VDD_4") (pintype "power_in"))
    )
    (net (code "40") (name "Net-(USB-MTN1)") (class "Default")
      (node (ref "L7") (pin "1") (pinfunction "1_1") (pintype "passive"))
      (node (ref "USB") (pin "MTN1") (pinfunction "MTN2_MTN1") (pintype "bidirectional"))
      (node (ref "USB") (pin "MTN2") (pinfunction "MTN3_MTN2") (pintype "bidirectional"))
      (node (ref "USB") (pin "MTN3") (pinfunction "MTN1_MTN3") (pintype "bidirectional"))
      (node (ref "USB") (pin "MTN4") (pinfunction "MTN4_MTN4") (pintype "bidirectional"))
    )
    (net (code "41") (name "PA00_XIN32") (class "Default")
      (node (ref "C23") (pin "2") (pinfunction "2_2") (pintype "passive"))
      (node (ref "IC2") (pin "1") (pinfunction "PA0/XIN32/EIC/SCOM1PAD0/TC2_1") (pintype "bidirectional"))
      (node (ref "Y4") (pin "P$1") (pinfunction "1_P$1") (pintype "bidirectional"))
    )
    (net (code "42") (name "PA01_XOUT32") (class "Default")
      (node (ref "C24") (pin "2") (pinfunction "2_2") (pintype "passive"))
      (node (ref "IC2") (pin "2") (pinfunction "PA1/XOUT32/EIC/SCOM1PAD1/TC2_2") (pintype "bidirectional"))
      (node (ref "Y4") (pin "P$2") (pinfunction "2_P$2") (pintype "bidirectional"))
    )
    (net (code "43") (name "PA02_AIN0") (class "Default")
      (node (ref "IC2") (pin "3") (pinfunction "PA2/EIC/AIN0_3") (pintype "bidirectional"))
      (node (ref "VDIV1") (pin "2") (pinfunction "2_2") (pintype "passive"))
      (node (ref "VDIV2") (pin "1") (pinfunction "1_1") (pintype "passive"))
    )
    (net (code "44") (name "PA03_AREFA") (class "Default")
      (node (ref "C4") (pin "1") (pinfunction "1_1") (pintype "passive"))
      (node (ref "C5") (pin "+") (pinfunction "+_+") (pintype "passive"))
      (node (ref "HEADER_IOH") (pin "8") (pinfunction "8_8") (pintype "passive"))
      (node (ref "IC2") (pin "4") (pinfunction "PA3/EIC/REF/AIN1_4") (pintype "bidirectional"))
    )
    (net (code "45") (name "PA04_AIN4") (class "Default")
      (node (ref "AD") (pin "4") (pinfunction "4_4") (pintype "passive"))
      (node (ref "IC2") (pin "9") (pinfunction "PA4/EIC/REF/AIN4/SCOM0PAD0/TC0_9") (pintype "bidirectional"))
    )
    (net (code "46") (name "PA05_AIN5") (class "Default")
      (node (ref "AD") (pin "5") (pinfunction "5_5") (pintype "passive"))
      (node (ref "IC2") (pin "10") (pinfunction "PA5/EIC/AIN5/SCOM0PAD1/TC0_10") (pintype "bidirectional"))
    )
    (net (code "47") (name "PA6_RFID_SHD") (class "Default")
      (node (ref "HEADER_IOH") (pin "1") (pinfunction "1_1") (pintype "passive"))
      (node (ref "IC2") (pin "11") (pinfunction "PA6/EIC/AIN6/SCOM0PAD2/TC1_11") (pintype "bidirectional"))
      (node (ref "RF_A") (pin "13") (pinfunction "STBY_13") (pintype "bidirectional"))
    )
    (net (code "48") (name "PA7_RFID_SHD2") (class "Default")
      (node (ref "HEADER_IOH") (pin "2") (pinfunction "2_2") (pintype "passive"))
      (node (ref "IC2") (pin "12") (pinfunction "PA7/EIC/AIN7/SCOM0PAD3/TC1_12") (pintype "bidirectional"))
      (node (ref "RF_B") (pin "13") (pinfunction "STBY_13") (pintype "bidirectional"))
    )
    (net (code "49") (name "PA08_TCC0-W0_PA8") (class "Default")
      (node (ref "HEADER_IOL") (pin "3") (pinfunction "3_3") (pintype "passive"))
      (node (ref "IC2") (pin "13") (pinfunction "PA8/I2C/AIN16/SCOM2PAD0+/TC0_13") (pintype "bidirectional"))
      (node (ref "MEM") (pin "4") (pinfunction "CS_4") (pintype "bidirectional"))
    )
    (net (code "50") (name "PA09_TCC0-W1_PA9") (class "Default")
      (node (ref "HEADER_IOL") (pin "4") (pinfunction "4_4") (pintype "passive"))
      (node (ref "IC2") (pin "14") (pinfunction "PA9/I2C/EIC/AIN17/SCOM2PAD1+/TC0_14") (pintype "bidirectional"))
    )
    (net (code "51") (name "PA10_TCC0-W2_PA10") (class "Default")
      (node (ref "HEADER_IOL") (pin "2") (pinfunction "2_2") (pintype "passive"))
      (node (ref "IC2") (pin "15") (pinfunction "PA10/EIC/AIN18/SCOM2PAD2+/TC1_15") (pintype "bidirectional"))
    )
    (net (code "52") (name "PA11_TCC0-W3_PA11") (class "Default")
      (node (ref "HEADER_IOL") (pin "1") (pinfunction "1_1") (pintype "passive"))
      (node (ref "IC2") (pin "16") (pinfunction "PA11/EIC/AIN19/SCOM2PAD3+/TC1_16") (pintype "bidirectional"))
    )
    (net (code "53") (name "PA13") (class "Default")
      (node (ref "HEADER_IOL") (pin "8") (pinfunction "8_8") (pintype "passive"))
      (node (ref "IC2") (pin "22") (pinfunction "PA13/I2C/EIC/SCOM2PAD1+/TC2_22") (pintype "bidirectional"))
    )
    (net (code "54") (name "PA14_TCC0-W4") (class "Default")
      (node (ref "HEADER_IOL") (pin "5") (pinfunction "5_5") (pintype "passive"))
      (node (ref "IC2") (pin "23") (pinfunction "PA14/XIN/EIC/SCOM2PAD2+/TC3_23") (pintype "bidirectional"))
    )
    (net (code "55") (name "PA15_TCC0-W5") (class "Default")
      (node (ref "HEADER_IOL") (pin "6") (pinfunction "6_6") (pintype "passive"))
      (node (ref "IC2") (pin "24") (pinfunction "PA15/XOUT/EIC/SCOM2PAD3+/TC3_24") (pintype "bidirectional"))
    )
    (net (code "56") (name "PA16_MOSI") (class "Default")
      (node (ref "HEADER_IOH") (pin "4") (pinfunction "4_4") (pintype "passive"))
      (node (ref "IC2") (pin "25") (pinfunction "PA16/I2C/EIC/SCOM1PAD0+/TC2_25") (pintype "bidirectional"))
    )
    (net (code "57") (name "PA17_SCK") (class "Default")
      (node (ref "HEADER_IOH") (pin "6") (pinfunction "6_6") (pintype "passive"))
      (node (ref "IC2") (pin "26") (pinfunction "PA17/I2C/EIC/SCOM1PAD1+/TC2_26") (pintype "bidirectional"))
    )
    (net (code "58") (name "PA18_SS") (class "Default")
      (node (ref "HEADER_IOH") (pin "3") (pinfunction "3_3") (pintype "passive"))
      (node (ref "IC2") (pin "27") (pinfunction "PA18/EIC/SCOM1PAD2+/TC3_27") (pintype "bidirectional"))
    )
    (net (code "59") (name "PA19_MISO") (class "Default")
      (node (ref "HEADER_IOH") (pin "5") (pinfunction "5_5") (pintype "passive"))
      (node (ref "IC2") (pin "28") (pinfunction "PA19/EIC/SCOM1PAD3+/TC3_28") (pintype "bidirectional"))
    )
    (net (code "60") (name "PA20_TCC0-W6") (class "Default")
      (node (ref "HEADER_IOL") (pin "7") (pinfunction "7_7") (pintype "passive"))
      (node (ref "IC2") (pin "29") (pinfunction "PA20/EIC/SCOM5PAD2+_29") (pintype "bidirectional"))
    )
    (net (code "61") (name "PA21_INT&SDCS") (class "Default")
      (node (ref "IC2") (pin "30") (pinfunction "PA21/EIC/SCOM5PAD3+_30") (pintype "bidirectional"))
      (node (ref "R9") (pin "1") (pinfunction "1_1") (pintype "passive"))
      (node (ref "RTC") (pin "7") (pinfunction "~{INT1/CLK}_7") (pintype "output"))
      (node (ref "U$4") (pin "1") (pinfunction "CS_1") (pintype "input"))
    )
    (net (code "62") (name "PA22_SDA") (class "Default")
      (node (ref "HEADER_IOH") (pin "9") (pinfunction "9_9") (pintype "passive"))
      (node (ref "IC2") (pin "31") (pinfunction "PA22/I2C/EIC/SCOM5PAD0+/TC4_31") (pintype "bidirectional"))
      (node (ref "R13") (pin "1") (pinfunction "1_1") (pintype "passive"))
      (node (ref "RTC") (pin "5") (pinfunction "SDA_5") (pintype "bidirectional"))
    )
    (net (code "63") (name "PA23_SCL") (class "Default")
      (node (ref "HEADER_IOH") (pin "10") (pinfunction "10_10") (pintype "passive"))
      (node (ref "IC2") (pin "32") (pinfunction "PA23/I2C/EIC/SCOM5PAD1+/TC4_32") (pintype "bidirectional"))
      (node (ref "R12") (pin "1") (pinfunction "1_1") (pintype "passive"))
      (node (ref "RTC") (pin "6") (pinfunction "SCL_6") (pintype "bidirectional"))
    )
    (net (code "64") (name "PA27_TX_LED") (class "Default")
      (node (ref "IC2") (pin "39") (pinfunction "PA27/EIC_39") (pintype "bidirectional"))
      (node (ref "R6") (pin "2") (pinfunction "2_2") (pintype "passive"))
    )
    (net (code "65") (name "PA28_2FETS") (class "Default")
      (node (ref "IC2") (pin "41") (pinfunction "PA28/EIC_41") (pintype "bidirectional"))
      (node (ref "R10") (pin "2") (pinfunction "2_2") (pintype "passive"))
      (node (ref "T_SD") (pin "1") (pinfunction "G_1") (pintype "passive"))
    )
    (net (code "66") (name "PA30_SWCLK") (class "Default")
      (node (ref "IC2") (pin "45") (pinfunction "PA30/EIC/SCOM1PAD2/TC1_45") (pintype "bidirectional"))
      (node (ref "ICSP!") (pin "4") (pinfunction "4_4") (pintype "passive"))
    )
    (net (code "67") (name "PA31_SWDIO") (class "Default")
      (node (ref "IC2") (pin "46") (pinfunction "PA31/EIC/SCOM1PAD3/TC1_46") (pintype "bidirectional"))
      (node (ref "ICSP!") (pin "2") (pinfunction "2_2") (pintype "passive"))
    )
    (net (code "68") (name "PB02") (class "Default")
      (node (ref "AD") (pin "6") (pinfunction "6_6") (pintype "passive"))
      (node (ref "IC2") (pin "47") (pinfunction "PB2/EIC/AIN10/SCOM5PAD0_47") (pintype "bidirectional"))
    )
    (net (code "69") (name "PB03_RFIDIN") (class "Default")
      (node (ref "IC2") (pin "48") (pinfunction "PB3/EIC/AIN11/SCOM5PAD1_48") (pintype "bidirectional"))
      (node (ref "RF_A") (pin "2") (pinfunction "OUTPUT_2") (pintype "bidirectional"))
      (node (ref "RF_B") (pin "2") (pinfunction "OUTPUT_2") (pintype "bidirectional"))
    )
    (net (code "70") (name "PB08_AIN2") (class "Default")
      (node (ref "AD") (pin "2") (pinfunction "2_2") (pintype "passive"))
      (node (ref "IC2") (pin "7") (pinfunction "PB8/EIC/AIN2/SCOM4PAD0/TC4_7") (pintype "bidirectional"))
    )
    (net (code "71") (name "PB09_AIN3") (class "Default")
      (node (ref "AD") (pin "3") (pinfunction "3_3") (pintype "passive"))
      (node (ref "IC2") (pin "8") (pinfunction "PB9/EIC/AIN3/SCOM4PAD1//TC4_8") (pintype "bidirectional"))
    )
    (net (code "72") (name "PB10_S4_SPI_MOSI") (class "Default")
      (node (ref "IC2") (pin "19") (pinfunction "PB10/EIC/SCOM4PAD2/TC5_19") (pintype "bidirectional"))
      (node (ref "ICSP") (pin "4") (pinfunction "4_4") (pintype "passive"))
      (node (ref "MEM") (pin "1") (pinfunction "SI_1") (pintype "bidirectional"))
      (node (ref "U$4") (pin "2") (pinfunction "DATA_IN_2") (pintype "input"))
    )
    (net (code "73") (name "PB11_S4_SPI_SCK") (class "Default")
      (node (ref "IC2") (pin "20") (pinfunction "PB11/EIC/SCOM4PAD3/TC5_20") (pintype "bidirectional"))
      (node (ref "ICSP") (pin "3") (pinfunction "3_3") (pintype "passive"))
      (node (ref "MEM") (pin "2") (pinfunction "SCK_2") (pintype "bidirectional"))
      (node (ref "U$4") (pin "5") (pinfunction "SCLK_5") (pintype "input"))
    )
    (net (code "74") (name "PB12_S4_SPI_MISO") (class "Default")
      (node (ref "IC2") (pin "21") (pinfunction "PA12/I2C/EIC/SCOM2PAD0+/TC2_21") (pintype "bidirectional"))
      (node (ref "ICSP") (pin "1") (pinfunction "1_1") (pintype "passive"))
      (node (ref "MEM") (pin "8") (pinfunction "SO_8") (pintype "bidirectional"))
      (node (ref "U$4") (pin "7") (pinfunction "DATA_OUT_7") (pintype "output"))
    )
    (net (code "75") (name "PB22_DEBUG_TX") (class "Default")
      (node (ref "IC2") (pin "37") (pinfunction "PB22/EIC/SCOM5PAD2_37") (pintype "bidirectional"))
      (node (ref "TP2") (pin "TP") (pinfunction "TP_TP") (pintype "input"))
    )
    (net (code "76") (name "PB23_DEBUG_RX") (class "Default")
      (node (ref "IC2") (pin "38") (pinfunction "PB23/EIC/SCOM5PAD3_38") (pintype "bidirectional"))
      (node (ref "TP1") (pin "TP") (pinfunction "TP_TP") (pintype "input"))
    )
    (net (code "77") (name "RESET") (class "Default")
      (node (ref "D2") (pin "A") (pinfunction "A_A") (pintype "passive"))
      (node (ref "HEADER_POWER") (pin "3") (pinfunction "3_3") (pintype "passive"))
      (node (ref "ICSP") (pin "5") (pinfunction "5_5") (pintype "passive"))
      (node (ref "ICSP!") (pin "10") (pinfunction "10_10") (pintype "passive"))
      (node (ref "R1") (pin "1") (pinfunction "1_1") (pintype "passive"))
      (node (ref "R2") (pin "2") (pinfunction "2_2") (pintype "passive"))
      (node (ref "RESET") (pin "3") (pinfunction "3_3") (pintype "passive"))
      (node (ref "RESET") (pin "4") (pinfunction "4_4") (pintype "passive"))
    )
    (net (code "78") (name "TARGET_RESET") (class "Default")
      (node (ref "C8") (pin "1") (pinfunction "1_1") (pintype "passive"))
      (node (ref "IC2") (pin "40") (pinfunction "RESETN_40") (pintype "bidirectional"))
      (node (ref "R2") (pin "1") (pinfunction "1_1") (pintype "passive"))
    )
    (net (code "79") (name "TARGET_USB_N") (class "Default")
      (node (ref "IC2") (pin "33") (pinfunction "PA24/EIC/SCOM3PAD2+/TC5_33") (pintype "bidirectional"))
      (node (ref "USB") (pin "D-") (pinfunction "D-_D-") (pintype "bidirectional"))
      (node (ref "Z6") (pin "1") (pinfunction "1_1") (pintype "passive"))
    )
    (net (code "80") (name "TARGET_USB_P") (class "Default")
      (node (ref "IC2") (pin "34") (pinfunction "PA25/EIC/SCOM3PAD3+/TC5_34") (pintype "bidirectional"))
      (node (ref "USB") (pin "D+") (pinfunction "D+_D+") (pintype "bidirectional"))
      (node (ref "Z5") (pin "1") (pinfunction "1_1") (pintype "passive"))
    )
    (net (code "81") (name "VDDCORE") (class "Default")
      (node (ref "C19") (pin "1") (pinfunction "1_1") (pintype "passive"))
      (node (ref "IC2") (pin "43") (pinfunction "VDDCORE1_43") (pintype "input"))
    )
    (net (code "82") (name "V_IN") (class "Default")
      (node (ref "C12V") (pin "1") (pinfunction "1_1") (pintype "passive"))
      (node (ref "C22_2") (pin "+") (pinfunction "+_+") (pintype "passive"))
      (node (ref "HEADER_POWER") (pin "8") (pinfunction "8_8") (pintype "passive"))
      (node (ref "LDO") (pin "IN") (pinfunction "VIN_IN") (pintype "input"))
      (node (ref "R7") (pin "1") (pinfunction "1_1") (pintype "passive"))
      (node (ref "RF_A") (pin "10") (pinfunction "VEXT_10") (pintype "bidirectional"))
      (node (ref "RF_A") (pin "11") (pinfunction "DVS_11") (pintype "bidirectional"))
      (node (ref "RF_B") (pin "10") (pinfunction "VEXT_10") (pintype "bidirectional"))
      (node (ref "RF_B") (pin "11") (pinfunction "DVS_11") (pintype "bidirectional"))
      (node (ref "U$9") (pin "P$3") (pinfunction "P_P$3") (pintype "passive"))
      (node (ref "VDIV2") (pin "2") (pinfunction "2_2") (pintype "passive"))
    )
    (net (code "83") (name "XUSB") (class "Default")
      (node (ref "C26") (pin "1") (pinfunction "1_1") (pintype "passive"))
      (node (ref "U$9") (pin "P$5") (pinfunction "S_P$5") (pintype "passive"))
      (node (ref "USB") (pin "VBUS") (pinfunction "VBUS_VBUS") (pintype "bidirectional"))
    )
    (net (code "84") (name "unconnected-(HEADER_POWER-Pad1)") (class "Default")
      (node (ref "HEADER_POWER") (pin "1") (pinfunction "1_1") (pintype "passive"))
    )
    (net (code "85") (name "unconnected-(ICSP!-Pad6)") (class "Default")
      (node (ref "ICSP!") (pin "6") (pinfunction "6_6") (pintype "passive"))
    )
    (net (code "86") (name "unconnected-(ICSP!-Pad7)") (class "Default")
      (node (ref "ICSP!") (pin "7") (pinfunction "7_7") (pintype "passive"))
    )
    (net (code "87") (name "unconnected-(ICSP!-Pad8)") (class "Default")
      (node (ref "ICSP!") (pin "8") (pinfunction "8_8") (pintype "passive"))
    )
    (net (code "88") (name "unconnected-(U$4-CARD_DETECT-PadCD)") (class "Default")
      (node (ref "U$4") (pin "CD") (pinfunction "CARD_DETECT_CD") (pintype "passive"))
    )
    (net (code "89") (name "unconnected-(U$4-DAT1-Pad8)") (class "Default")
      (node (ref "U$4") (pin "8") (pinfunction "DAT1_8") (pintype "bidirectional"))
    )
    (net (code "90") (name "unconnected-(U$4-DAT2-Pad9)") (class "Default")
      (node (ref "U$4") (pin "9") (pinfunction "DAT2_9") (pintype "bidirectional"))
    )
    (net (code "91") (name "unconnected-(U$4-WRITE_PROTECT-PadWP)") (class "Default")
      (node (ref "U$4") (pin "WP") (pinfunction "WRITE_PROTECT_WP") (pintype "passive"))
    )
    (net (code "92") (name "unconnected-(U$9-O1-PadP$2)") (class "Default")
      (node (ref "U$9") (pin "P$2") (pinfunction "O1_P$2") (pintype "passive"))
    )
    (net (code "93") (name "unconnected-(U$9-P1-PadP$4)") (class "Default")
      (node (ref "U$9") (pin "P$4") (pinfunction "P1_P$4") (pintype "passive"))
    )
    (net (code "94") (name "unconnected-(U$9-S1-PadP$6)") (class "Default")
      (node (ref "U$9") (pin "P$6") (pinfunction "S1_P$6") (pintype "passive"))
    )
    (net (code "95") (name "unconnected-(USB-PadID)") (class "Default")
      (node (ref "USB") (pin "ID") (pinfunction "ID_ID") (pintype "bidirectional"))
    )
  )
)
